# airu-board_1.net
KiCad netlist of a schematic drawn in Altium Designer
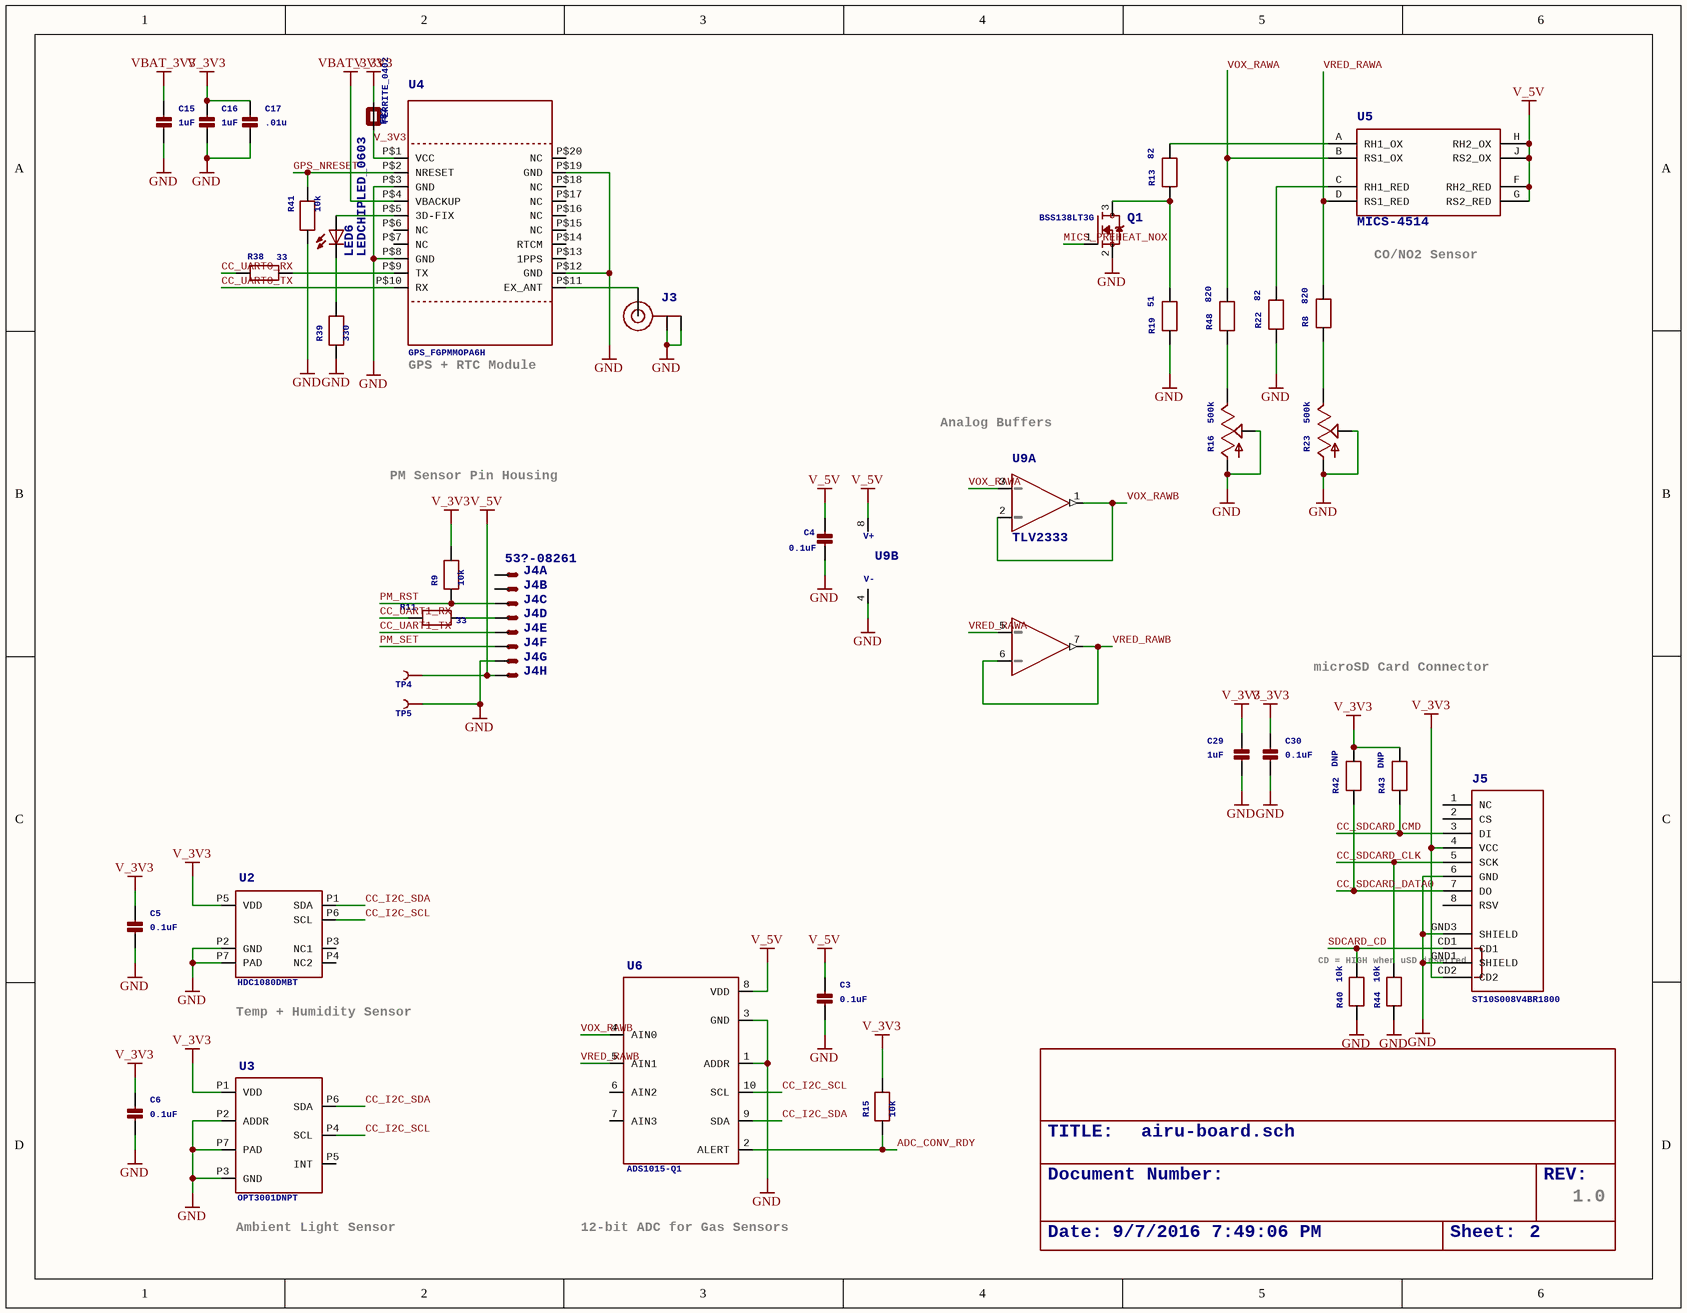
[diagram p0: airu-board_1.SchDoc]

(export (version "E")
  (design (tool "Eeschema 10.0.6"))
  (components
    (comp (ref "C3")
      (value "0.1uF")
      (footprint "_0402")
      (libsource (lib "microbuilder") (part "CAP_CERAMIC_0402"))
    )
    (comp (ref "C4")
      (value "0.1uF")
      (footprint "_0402")
      (libsource (lib "microbuilder") (part "CAP_CERAMIC_0402"))
    )
    (comp (ref "C5")
      (value "0.1uF")
      (footprint "_0402")
      (libsource (lib "microbuilder") (part "CAP_CERAMIC_0402"))
    )
    (comp (ref "C6")
      (value "0.1uF")
      (footprint "_0402")
      (libsource (lib "microbuilder") (part "CAP_CERAMIC_0402"))
    )
    (comp (ref "C15")
      (value "1uF")
      (footprint "_0402")
      (libsource (lib "microbuilder") (part "CAP_CERAMIC_0402"))
    )
    (comp (ref "C16")
      (value "1uF")
      (footprint "_0402")
      (libsource (lib "microbuilder") (part "CAP_CERAMIC_0402"))
    )
    (comp (ref "C17")
      (value ".01u")
      (footprint "_0402")
      (libsource (lib "microbuilder") (part "CAP_CERAMIC_0402"))
    )
    (comp (ref "C29") (value "1uF") (footprint "_0402") (libsource (lib "") (part "CAP_CERAMIC_0402_1")))
    (comp (ref "C30")
      (value "0.1uF")
      (footprint "_0402")
      (libsource (lib "microbuilder") (part "CAP_CERAMIC_0402"))
    )
    (comp (ref "FB2")
      (value "FERRITE_0402")
      (footprint "_0402")
      (libsource (lib "microbuilder") (part "FERRITE_0402"))
    )
    (comp (ref "FRAME3")
      (value "FRAME_A_L")
      (description "<b>FRAME</b> A Size , 8 1/2 x 11 INCH, Landscape<p>")
      (fields
        (field (name "DATE:") "Date:")
        (field (name ">LAST_DATE_TIME") "9/7/2016 7:49:06 PM")
        (field (name "SHEET:") "Sheet:")
        (field (name ">SHEET") "2")
        (field (name "REV:") "REV:")
        (field (name "TITLE:") "TITLE:")
        (field (name "DOCUMENT NUMBER:") "Document Number:")
        (field (name ">DRAWING_NAME") "airu-board.sch")
      )
      (libsource (lib "frames") (part "FRAME_A_L"))
    )
    (comp (ref "J3")
      (value "U.FL-R-SMT-1(10)")
      (footprint "U.FL")
      (description "<p>U.FL Antenna Connector</p>")
      (libsource (lib "microbuilder") (part "U.FL"))
    )
    (comp (ref "J4")
      (value "53?-08261")
      (footprint "53261-08")
      (description "<b>CONNECTOR</b><p>\nwire to board 1.25 mm (.049 inch) pitch header")
      (libsource (lib "con-molex") (part "53?-08261"))
    )
    (comp (ref "J5")
      (value "ST10S008V4BR1800")
      (footprint "MICROSD_1:1")
      (libsource (lib "SparkFun-Connectors") (part "USD-SOCKET"))
    )
    (comp (ref "LED6")
      (value "LEDCHIPLED_0603")
      (footprint "CHIPLED_0603")
      (libsource (lib "led") (part "LEDCHIPLED_0603"))
    )
    (comp (ref "Q1")
      (value "BSS138LT3G")
      (footprint "SOT23")
      (libsource (lib "adafruit") (part "MOSFET-NREFLOW"))
    )
    (comp (ref "R8") (value "820") (footprint "0402") (libsource (lib "microbuilder") (part "RESISTOR0402")))
    (comp (ref "R9") (value "10k") (footprint "0402") (libsource (lib "microbuilder") (part "RESISTOR0402")))
    (comp (ref "R11") (value "33") (footprint "0402") (libsource (lib "microbuilder") (part "RESISTOR0402")))
    (comp (ref "R13") (value "82") (footprint "0402") (libsource (lib "microbuilder") (part "RESISTOR0402")))
    (comp (ref "R15") (value "10k") (footprint "0402") (libsource (lib "microbuilder") (part "RESISTOR0402")))
    (comp (ref "R16")
      (value "500k")
      (footprint "B25P")
      (description "<b>POTENTIOMETER</b>")
      (libsource (lib "pot") (part "TRIM_US-B25P"))
    )
    (comp (ref "R19") (value "51") (footprint "0402") (libsource (lib "microbuilder") (part "RESISTOR0402")))
    (comp (ref "R22") (value "82") (footprint "0402") (libsource (lib "microbuilder") (part "RESISTOR0402")))
    (comp (ref "R23")
      (value "500k")
      (footprint "B25P")
      (description "<b>POTENTIOMETER</b>")
      (libsource (lib "pot") (part "TRIM_US-B25P"))
    )
    (comp (ref "R38") (value "33") (footprint "0402") (libsource (lib "microbuilder") (part "RESISTOR0402")))
    (comp (ref "R39") (value "330") (footprint "0402") (libsource (lib "microbuilder") (part "RESISTOR0402")))
    (comp (ref "R40") (value "10k") (footprint "0402") (libsource (lib "microbuilder") (part "RESISTOR0402")))
    (comp (ref "R41") (value "10k") (footprint "0402") (libsource (lib "microbuilder") (part "RESISTOR0402")))
    (comp (ref "R42") (value "DNP") (footprint "0402") (libsource (lib "microbuilder") (part "RESISTOR0402")))
    (comp (ref "R43") (value "DNP") (footprint "0402") (libsource (lib "microbuilder") (part "RESISTOR0402")))
    (comp (ref "R44") (value "10k") (footprint "0402") (libsource (lib "microbuilder") (part "RESISTOR0402")))
    (comp (ref "R48") (value "820") (footprint "0402") (libsource (lib "microbuilder") (part "RESISTOR0402")))
    (comp (ref "TP4")
      (value "TEST-POINT2")
      (footprint "PAD.02X.02")
      (description "Bare copper test points for troubleshooting or ICT")
      (libsource (lib "SparkFun-Passives") (part "TEST-POINT2"))
    )
    (comp (ref "TP5")
      (value "TEST-POINT2")
      (footprint "PAD.02X.02")
      (description "Bare copper test points for troubleshooting or ICT")
      (libsource (lib "SparkFun-Passives") (part "TEST-POINT2"))
    )
    (comp (ref "U2") (value "HDC1080DMBT") (footprint "WSON") (libsource (lib "texas") (part "HDC1080")))
    (comp (ref "U3") (value "OPT3001DNPT") (footprint "USON") (libsource (lib "texas") (part "OPT3001")))
    (comp (ref "U4")
      (value "GPS_FGPMMOPA6H")
      (footprint "FGPMMOPA6H")
      (libsource (lib "microbuilder") (part "GPS_FGPMMOPA6H"))
    )
    (comp (ref "U5")
      (value "MICS-4514")
      (footprint "MICS_10-SMD")
      (description "Metal oxide MEMS carbon monoxide (CO) and NOx sensor in an SMD package.")
      (libsource (lib "SparkFun-Sensors") (part "MICS-4514"))
    )
    (comp (ref "U6") (value "ADS1015-Q1") (footprint "S-PDSO-G10") (libsource (lib "texas") (part "ADS1015")))
    (comp (ref "U9")
      (value "TLV2333")
      (footprint "DGK_S-PDSO-G8")
      (fields (field (name "V+") "V+") (field (name "V-") "V-"))
      (libsource (lib "texas") (part "TLV2333"))
    )
  )
  (nets
    (net (code "1") (name "/ADC_CONV_RDY") (class "Default")
      (node (ref "R15") (pin "1") (pinfunction "1_1") (pintype "passive"))
      (node (ref "U6") (pin "2") (pinfunction "ALERT_2") (pintype "passive"))
    )
    (net (code "2") (name "/CC_I2C_SCL") (class "Default")
      (node (ref "U2") (pin "P6") (pinfunction "SCL_P6") (pintype "passive"))
      (node (ref "U3") (pin "P4") (pinfunction "SCL_P4") (pintype "passive"))
      (node (ref "U6") (pin "10") (pinfunction "SCL_10") (pintype "passive"))
    )
    (net (code "3") (name "/CC_I2C_SDA") (class "Default")
      (node (ref "U2") (pin "P1") (pinfunction "SDA_P1") (pintype "passive"))
      (node (ref "U3") (pin "P6") (pinfunction "SDA_P6") (pintype "passive"))
      (node (ref "U6") (pin "9") (pinfunction "SDA_9") (pintype "passive"))
    )
    (net (code "4") (name "/CC_SDCARD_CLK") (class "Default")
      (node (ref "J5") (pin "5") (pinfunction "SCK_5") (pintype "passive"))
      (node (ref "R44") (pin "2") (pinfunction "2_2") (pintype "passive"))
    )
    (net (code "5") (name "/CC_SDCARD_CMD") (class "Default")
      (node (ref "J5") (pin "3") (pinfunction "DI_3") (pintype "passive"))
      (node (ref "R43") (pin "1") (pinfunction "1_1") (pintype "passive"))
    )
    (net (code "6") (name "/CC_SDCARD_DATA0") (class "Default")
      (node (ref "J5") (pin "7") (pinfunction "DO_7") (pintype "passive"))
      (node (ref "R42") (pin "1") (pinfunction "1_1") (pintype "passive"))
    )
    (net (code "7") (name "/CC_UART0_RX") (class "Default")
      (node (ref "R38") (pin "1") (pinfunction "1_1") (pintype "passive"))
    )
    (net (code "8") (name "/CC_UART0_TX") (class "Default")
      (node (ref "U4") (pin "P$10") (pinfunction "RX_P$10") (pintype "passive"))
    )
    (net (code "9") (name "/CC_UART1_RX") (class "Default")
      (node (ref "R11") (pin "1") (pinfunction "1_1") (pintype "passive"))
    )
    (net (code "10") (name "/CC_UART1_TX") (class "Default")
      (node (ref "J4") (pin "5") (pinfunction "S_5") (pintype "passive"))
    )
    (net (code "11") (name "/GPS_NRESET") (class "Default")
      (node (ref "R41") (pin "2") (pinfunction "2_2") (pintype "passive"))
      (node (ref "U4") (pin "P$2") (pinfunction "NRESET_P$2") (pintype "passive"))
    )
    (net (code "12") (name "/MICS_PREHEAT_NOX") (class "Default")
      (node (ref "Q1") (pin "1") (pinfunction "G_1") (pintype "passive"))
    )
    (net (code "13") (name "/PM_RST") (class "Default")
      (node (ref "J4") (pin "3") (pinfunction "S_3") (pintype "passive"))
      (node (ref "R9") (pin "1") (pinfunction "1_1") (pintype "passive"))
    )
    (net (code "14") (name "/PM_SET") (class "Default")
      (node (ref "J4") (pin "6") (pinfunction "S_6") (pintype "passive"))
    )
    (net (code "15") (name "/SDCARD_CD") (class "Default")
      (node (ref "J5") (pin "CD1") (pinfunction "CD1_CD1") (pintype "passive"))
      (node (ref "R40") (pin "2") (pinfunction "2_2") (pintype "passive"))
    )
    (net (code "16") (name "/VOX_RAWA") (class "Default")
      (node (ref "R48") (pin "2") (pinfunction "2_2") (pintype "passive"))
      (node (ref "U5") (pin "B") (pinfunction "RS1_OX_B") (pintype "passive"))
      (node (ref "U9") (pin "3") (pinfunction "+_3") (pintype "passive"))
    )
    (net (code "17") (name "/VOX_RAWB") (class "Default")
      (node (ref "U6") (pin "4") (pinfunction "AIN0_4") (pintype "passive"))
      (node (ref "U9") (pin "1") (pinfunction "OUT_1") (pintype "output"))
      (node (ref "U9") (pin "2") (pinfunction "-_2") (pintype "passive"))
    )
    (net (code "18") (name "/VRED_RAWA") (class "Default")
      (node (ref "R8") (pin "2") (pinfunction "2_2") (pintype "passive"))
      (node (ref "U5") (pin "D") (pinfunction "RS1_RED_D") (pintype "passive"))
      (node (ref "U9") (pin "5") (pinfunction "+1_5") (pintype "passive"))
    )
    (net (code "19") (name "/VRED_RAWB") (class "Default")
      (node (ref "U6") (pin "5") (pinfunction "AIN1_5") (pintype "passive"))
      (node (ref "U9") (pin "6") (pinfunction "-1_6") (pintype "passive"))
      (node (ref "U9") (pin "7") (pinfunction "OUT1_7") (pintype "output"))
    )
    (net (code "20") (name "GND") (class "Default")
      (node (ref "C15") (pin "2") (pinfunction "P$2_2") (pintype "passive"))
      (node (ref "C16") (pin "2") (pinfunction "P$2_2") (pintype "passive"))
      (node (ref "C17") (pin "2") (pinfunction "P$2_2") (pintype "passive"))
      (node (ref "C29") (pin "2") (pinfunction "P$2_2") (pintype "passive"))
      (node (ref "C3") (pin "2") (pinfunction "P$2_2") (pintype "passive"))
      (node (ref "C30") (pin "2") (pinfunction "P$2_2") (pintype "passive"))
      (node (ref "C4") (pin "2") (pinfunction "P$2_2") (pintype "passive"))
      (node (ref "C5") (pin "2") (pinfunction "P$2_2") (pintype "passive"))
      (node (ref "C6") (pin "2") (pinfunction "P$2_2") (pintype "passive"))
      (node (ref "J3") (pin "1") (pinfunction "GND_1") (pintype "passive"))
      (node (ref "J3") (pin "2") (pinfunction "GND_2") (pintype "passive"))
      (node (ref "J4") (pin "7") (pinfunction "S_7") (pintype "passive"))
      (node (ref "J5") (pin "6") (pinfunction "GND_6") (pintype "passive"))
      (node (ref "J5") (pin "GND1") (pinfunction "SHIELD_GND1") (pintype "passive"))
      (node (ref "J5") (pin "GND3") (pinfunction "SHIELD_GND3") (pintype "passive"))
      (node (ref "Q1") (pin "2") (pinfunction "S_2") (pintype "passive"))
      (node (ref "R16") (pin "A") (pinfunction "A_A") (pintype "passive"))
      (node (ref "R16") (pin "S") (pinfunction "S_S") (pintype "passive"))
      (node (ref "R19") (pin "1") (pinfunction "1_1") (pintype "passive"))
      (node (ref "R22") (pin "1") (pinfunction "1_1") (pintype "passive"))
      (node (ref "R23") (pin "A") (pinfunction "A_A") (pintype "passive"))
      (node (ref "R23") (pin "S") (pinfunction "S_S") (pintype "passive"))
      (node (ref "R39") (pin "1") (pinfunction "1_1") (pintype "passive"))
      (node (ref "R40") (pin "1") (pinfunction "1_1") (pintype "passive"))
      (node (ref "R41") (pin "1") (pinfunction "1_1") (pintype "passive"))
      (node (ref "R44") (pin "1") (pinfunction "1_1") (pintype "passive"))
      (node (ref "TP5") (pin "P$1") (pinfunction "1_P$1") (pintype "passive"))
      (node (ref "U2") (pin "P2") (pinfunction "GND_P2") (pintype "power_in"))
      (node (ref "U2") (pin "P7") (pinfunction "PAD_P7") (pintype "power_in"))
      (node (ref "U3") (pin "P2") (pinfunction "ADDR_P2") (pintype "passive"))
      (node (ref "U3") (pin "P3") (pinfunction "GND_P3") (pintype "power_in"))
      (node (ref "U3") (pin "P7") (pinfunction "PAD_P7") (pintype "power_in"))
      (node (ref "U4") (pin "P$12") (pinfunction "GND_P$12") (pintype "passive"))
      (node (ref "U4") (pin "P$19") (pinfunction "GND_P$19") (pintype "passive"))
      (node (ref "U4") (pin "P$3") (pinfunction "GND_P$3") (pintype "passive"))
      (node (ref "U4") (pin "P$8") (pinfunction "GND_P$8") (pintype "passive"))
      (node (ref "U6") (pin "1") (pinfunction "ADDR_1") (pintype "passive"))
      (node (ref "U6") (pin "3") (pinfunction "GND_3") (pintype "power_in"))
      (node (ref "U9") (pin "4") (pinfunction "V-_4") (pintype "power_in"))
    )
    (net (code "21") (name "Net-(J3-SIGNAL)") (class "Default")
      (node (ref "J3") (pin "3") (pinfunction "SIGNAL_3") (pintype "passive"))
      (node (ref "U4") (pin "P$11") (pinfunction "EX_ANT_P$11") (pintype "passive"))
    )
    (net (code "22") (name "Net-(J4D-S)") (class "Default")
      (node (ref "J4") (pin "4") (pinfunction "S_4") (pintype "passive"))
      (node (ref "R11") (pin "2") (pinfunction "2_2") (pintype "passive"))
    )
    (net (code "23") (name "Net-(LED6-PadC)") (class "Default")
      (node (ref "LED6") (pin "C") (pinfunction "C_C") (pintype "passive"))
      (node (ref "R39") (pin "2") (pinfunction "2_2") (pintype "passive"))
    )
    (net (code "24") (name "Net-(Q1-D)") (class "Default")
      (node (ref "Q1") (pin "3") (pinfunction "D_3") (pintype "passive"))
      (node (ref "R13") (pin "1") (pinfunction "1_1") (pintype "passive"))
      (node (ref "R19") (pin "2") (pinfunction "2_2") (pintype "passive"))
    )
    (net (code "25") (name "Net-(R16-PadE)") (class "Default")
      (node (ref "R16") (pin "E") (pinfunction "E_E") (pintype "passive"))
      (node (ref "R48") (pin "1") (pinfunction "1_1") (pintype "passive"))
    )
    (net (code "26") (name "Net-(R23-PadE)") (class "Default")
      (node (ref "R23") (pin "E") (pinfunction "E_E") (pintype "passive"))
      (node (ref "R8") (pin "1") (pinfunction "1_1") (pintype "passive"))
    )
    (net (code "27") (name "Net-(U4-3D-FIX)") (class "Default")
      (node (ref "LED6") (pin "A") (pinfunction "A_A") (pintype "passive"))
      (node (ref "U4") (pin "P$5") (pinfunction "3D-FIX_P$5") (pintype "passive"))
    )
    (net (code "28") (name "Net-(U4-TX)") (class "Default")
      (node (ref "R38") (pin "2") (pinfunction "2_2") (pintype "passive"))
      (node (ref "U4") (pin "P$9") (pinfunction "TX_P$9") (pintype "passive"))
    )
    (net (code "29") (name "Net-(U5-RH1_OX)") (class "Default")
      (node (ref "R13") (pin "2") (pinfunction "2_2") (pintype "passive"))
      (node (ref "U5") (pin "A") (pinfunction "RH1_OX_A") (pintype "passive"))
    )
    (net (code "30") (name "Net-(U5-RH1_RED)") (class "Default")
      (node (ref "R22") (pin "2") (pinfunction "2_2") (pintype "passive"))
      (node (ref "U5") (pin "C") (pinfunction "RH1_RED_C") (pintype "passive"))
    )
    (net (code "31") (name "VBAT_3V3") (class "Default")
      (node (ref "C15") (pin "1") (pinfunction "P$1_1") (pintype "passive"))
      (node (ref "U4") (pin "P$4") (pinfunction "VBACKUP_P$4") (pintype "passive"))
    )
    (net (code "32") (name "V_3V3") (class "Default")
      (node (ref "C16") (pin "1") (pinfunction "P$1_1") (pintype "passive"))
      (node (ref "C17") (pin "1") (pinfunction "P$1_1") (pintype "passive"))
      (node (ref "C29") (pin "1") (pinfunction "P$1_1") (pintype "passive"))
      (node (ref "C30") (pin "1") (pinfunction "P$1_1") (pintype "passive"))
      (node (ref "C5") (pin "1") (pinfunction "P$1_1") (pintype "passive"))
      (node (ref "C6") (pin "1") (pinfunction "P$1_1") (pintype "passive"))
      (node (ref "FB2") (pin "1") (pinfunction "P$1_1") (pintype "passive"))
      (node (ref "FB2") (pin "2") (pinfunction "P$2_2") (pintype "passive"))
      (node (ref "J5") (pin "4") (pinfunction "VCC_4") (pintype "passive"))
      (node (ref "J5") (pin "CD2") (pinfunction "CD2_CD2") (pintype "passive"))
      (node (ref "R15") (pin "2") (pinfunction "2_2") (pintype "passive"))
      (node (ref "R42") (pin "2") (pinfunction "2_2") (pintype "passive"))
      (node (ref "R43") (pin "2") (pinfunction "2_2") (pintype "passive"))
      (node (ref "R9") (pin "2") (pinfunction "2_2") (pintype "passive"))
      (node (ref "U2") (pin "P5") (pinfunction "VDD_P5") (pintype "power_in"))
      (node (ref "U3") (pin "P1") (pinfunction "VDD_P1") (pintype "power_in"))
      (node (ref "U4") (pin "P$1") (pinfunction "VCC_P$1") (pintype "passive"))
    )
    (net (code "33") (name "V_5V") (class "Default")
      (node (ref "C3") (pin "1") (pinfunction "P$1_1") (pintype "passive"))
      (node (ref "C4") (pin "1") (pinfunction "P$1_1") (pintype "passive"))
      (node (ref "J4") (pin "8") (pinfunction "S_8") (pintype "passive"))
      (node (ref "TP4") (pin "P$1") (pinfunction "1_P$1") (pintype "passive"))
      (node (ref "U5") (pin "F") (pinfunction "RH2_RED_F") (pintype "passive"))
      (node (ref "U5") (pin "G") (pinfunction "RS2_RED_G") (pintype "passive"))
      (node (ref "U5") (pin "H") (pinfunction "RH2_OX_H") (pintype "passive"))
      (node (ref "U5") (pin "J") (pinfunction "RS2_OX_J") (pintype "passive"))
      (node (ref "U6") (pin "8") (pinfunction "VDD_8") (pintype "power_in"))
      (node (ref "U9") (pin "8") (pinfunction "V+_8") (pintype "power_in"))
    )
    (net (code "34") (name "unconnected-(J4A-S-Pad1)") (class "Default")
      (node (ref "J4") (pin "1") (pinfunction "S_1") (pintype "passive"))
    )
    (net (code "35") (name "unconnected-(J4B-S-Pad2)") (class "Default")
      (node (ref "J4") (pin "2") (pinfunction "S_2") (pintype "passive"))
    )
    (net (code "36") (name "unconnected-(J5-CS-Pad2)") (class "Default")
      (node (ref "J5") (pin "2") (pinfunction "CS_2") (pintype "passive"))
    )
    (net (code "37") (name "unconnected-(J5-NC-Pad1)") (class "Default")
      (node (ref "J5") (pin "1") (pinfunction "NC_1") (pintype "passive"))
    )
    (net (code "38") (name "unconnected-(J5-RSV-Pad8)") (class "Default")
      (node (ref "J5") (pin "8") (pinfunction "RSV_8") (pintype "passive"))
    )
    (net (code "39") (name "unconnected-(U2-NC1-PadP3)") (class "Default")
      (node (ref "U2") (pin "P3") (pinfunction "NC1_P3") (pintype "passive"))
    )
    (net (code "40") (name "unconnected-(U2-NC2-PadP4)") (class "Default")
      (node (ref "U2") (pin "P4") (pinfunction "NC2_P4") (pintype "passive"))
    )
    (net (code "41") (name "unconnected-(U3-INT-PadP5)") (class "Default")
      (node (ref "U3") (pin "P5") (pinfunction "INT_P5") (pintype "passive"))
    )
    (net (code "42") (name "unconnected-(U4-1PPS-PadP$13)") (class "Default")
      (node (ref "U4") (pin "P$13") (pinfunction "1PPS_P$13") (pintype "passive"))
    )
    (net (code "43") (name "unconnected-(U4-NC-PadP$6)") (class "Default")
      (node (ref "U4") (pin "P$6") (pinfunction "NC_P$6") (pintype "passive"))
    )
    (net (code "44") (name "unconnected-(U4-NC-PadP$7)") (class "Default")
      (node (ref "U4") (pin "P$7") (pinfunction "NC_P$7") (pintype "passive"))
    )
    (net (code "45") (name "unconnected-(U4-NC-PadP$15)") (class "Default")
      (node (ref "U4") (pin "P$15") (pinfunction "NC_P$15") (pintype "passive"))
    )
    (net (code "46") (name "unconnected-(U4-NC-PadP$16)") (class "Default")
      (node (ref "U4") (pin "P$16") (pinfunction "NC_P$16") (pintype "passive"))
    )
    (net (code "47") (name "unconnected-(U4-NC-PadP$17)") (class "Default")
      (node (ref "U4") (pin "P$17") (pinfunction "NC_P$17") (pintype "passive"))
    )
    (net (code "48") (name "unconnected-(U4-NC-PadP$18)") (class "Default")
      (node (ref "U4") (pin "P$18") (pinfunction "NC_P$18") (pintype "passive"))
    )
    (net (code "49") (name "unconnected-(U4-NC-PadP$20)") (class "Default")
      (node (ref "U4") (pin "P$20") (pinfunction "NC_P$20") (pintype "passive"))
    )
    (net (code "50") (name "unconnected-(U4-RTCM-PadP$14)") (class "Default")
      (node (ref "U4") (pin "P$14") (pinfunction "RTCM_P$14") (pintype "passive"))
    )
    (net (code "51") (name "unconnected-(U6-AIN2-Pad6)") (class "Default")
      (node (ref "U6") (pin "6") (pinfunction "AIN2_6") (pintype "passive"))
    )
    (net (code "52") (name "unconnected-(U6-AIN3-Pad7)") (class "Default")
      (node (ref "U6") (pin "7") (pinfunction "AIN3_7") (pintype "passive"))
    )
  )
)
